# Housekeeping.net
KiCad netlist of a schematic drawn in Altium Designer
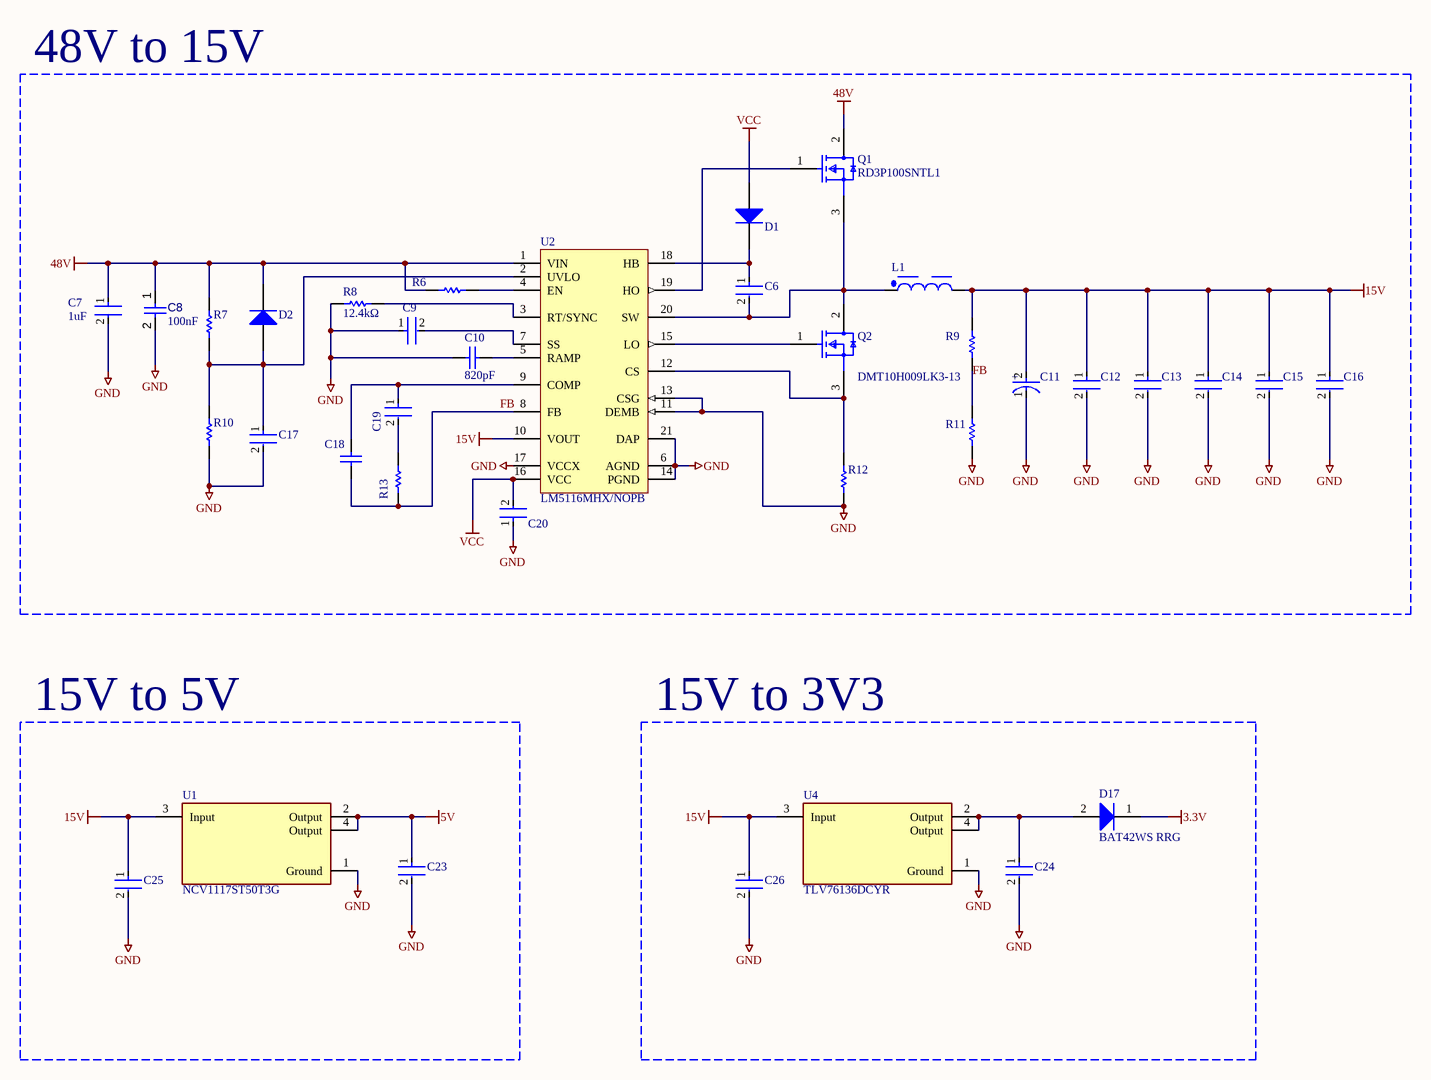
[diagram p0: Housekeeping.SchDoc]

(export (version "E")
  (design (tool "Eeschema 10.0.6"))
  (components
    (comp (ref "C6")
      (value "UMK107AB7105KA-T")
      (footprint "FP-0603-L_1_6_0_15-W_0_8-IPC_C")
      (description "Ceramic Capacitor General Use 1uF ±10% 50V X7R 0603")
      (fields (field (name "TOLERANCE") "10%"))
      (libsource (lib "Altium Content Vault") (part "11868f565c42a9108669ba33697ecf6"))
    )
    (comp (ref "C7")
      (value "C1210C105K1RACTU")
      (footprint "FP-C1210C105K1RACTU-MFG")
      (description "CAP CER 1UF 100V X7R 1210")
      (fields
        (field (name "CAPACITANCE") "1uF")
        (field (name "VOLTAGE") "100V")
        (field (name "TOLERANCE") "10%")
      )
      (libsource (lib "Altium Content Vault") (part "b4654b650e69147ec39a6b967a45e02"))
    )
    (comp (ref "C8")
      (value "100nF")
      (footprint "FP-CL10-IPC_B")
      (fields (field (name "Comment") "CL10B104KC8NNNC"))
      (libsource (lib "CEV Electrical") (part "CAP-NP-2"))
    )
    (comp (ref "C9")
      (value "CL10B104KC8NNNC")
      (footprint "FP-CL10-IPC_A")
      (description "Cap Ceramic 100nF 100V X7R ±10% Pad SMD 0603 +125°C T/R")
      (fields (field (name "TOLERANCE") "10%"))
      (libsource (lib "Altium Content Vault") (part "b4654b650e69147ec39a6b967a45e02"))
    )
    (comp (ref "C10")
      (value "820pF")
      (footprint "0603N821J500CT-Footprint-1")
      (description "0603 Cap Ceramic 820pF 50V C0G 5% - Multilayer Ceramic Capacitors")
      (fields (field (name "TOLERANCE") "5%") (field (name "Comment") "0603N821J500CT"))
      (libsource (lib "CEV Electrical New") (part "0603N821J500CT-Symbol-1"))
    )
    (comp (ref "C11")
      (value "50SVPF10M")
      (footprint "FP-OS-CON-SMT-C6-MFG")
      (description "Conductive Polymer Aluminum Solid Capacitors (OS-CON) 10uF ±20% 50V")
      (fields (field (name "VOLTAGE") "50V") (field (name "TOLERANCE") "20%"))
      (libsource (lib "Altium Content Vault") (part "a00bbbee19879c290e62620ae7e47b1"))
    )
    (comp (ref "C12")
      (value "CL31A106KBHNNNE")
      (footprint "FP-CL31-IPC_C")
      (description "CAP CER 10UF 50V X5R 1206")
      (fields (field (name "TOLERANCE") "10%") (field (name "MANUFACTURER") "Samsung"))
      (libsource (lib "Altium Content Vault") (part "11868f565c42a9108669ba33697ecf6"))
    )
    (comp (ref "C13")
      (value "CL31A106KBHNNNE")
      (footprint "FP-CL31-IPC_C")
      (description "CAP CER 10UF 50V X5R 1206")
      (fields (field (name "TOLERANCE") "10%") (field (name "MANUFACTURER") "Samsung"))
      (libsource (lib "Altium Content Vault") (part "11868f565c42a9108669ba33697ecf6"))
    )
    (comp (ref "C14")
      (value "CL31A106KBHNNNE")
      (footprint "FP-CL31-IPC_C")
      (description "CAP CER 10UF 50V X5R 1206")
      (fields (field (name "TOLERANCE") "10%") (field (name "MANUFACTURER") "Samsung"))
      (libsource (lib "Altium Content Vault") (part "11868f565c42a9108669ba33697ecf6"))
    )
    (comp (ref "C15")
      (value "CL31A106KBHNNNE")
      (footprint "FP-CL31-IPC_C")
      (description "CAP CER 10UF 50V X5R 1206")
      (fields (field (name "TOLERANCE") "10%") (field (name "MANUFACTURER") "Samsung"))
      (libsource (lib "Altium Content Vault") (part "11868f565c42a9108669ba33697ecf6"))
    )
    (comp (ref "C16")
      (value "CL31A106KBHNNNE")
      (footprint "FP-CL31-IPC_C")
      (description "CAP CER 10UF 50V X5R 1206")
      (fields (field (name "TOLERANCE") "10%") (field (name "MANUFACTURER") "Samsung"))
      (libsource (lib "Altium Content Vault") (part "11868f565c42a9108669ba33697ecf6"))
    )
    (comp (ref "C17")
      (value "UMK107AB7105KA-T")
      (footprint "FP-0603-L_1_6_0_15-W_0_8-IPC_C")
      (description "Ceramic Capacitor General Use 1uF ±10% 50V X7R 0603")
      (fields (field (name "TOLERANCE") "10%"))
      (libsource (lib "Altium Content Vault") (part "11868f565c42a9108669ba33697ecf6"))
    )
    (comp (ref "C18")
      (value "CC0603JRNPO9BN101")
      (footprint "CAPC1608X90X40ML10T20")
      (description "Chip Capacitor, 100 pF, +/- 5%, 50 V, -55 to 125 degC, 0603 (1608 Metric), RoHS, Tape and Reel")
      (fields (field (name "TOLERANCE") "5%") (field (name "VOLTAGE") "50V"))
      (libsource (lib "Altium Content Vault") (part "CAP-NP-2"))
    )
    (comp (ref "C19")
      (value "C0603C332J5RACTU")
      (footprint "FP-C0603C-CF-MFG")
      (description "CAP CER 3300PF 50V 5% X7R 0603")
      (fields (field (name "MANUFACTURER") "KEMET") (field (name "TOLERANCE") "0.05"))
      (libsource (lib "Altium Content Vault") (part "b4654b650e69147ec39a6b967a45e02"))
    )
    (comp (ref "C20")
      (value "UMK107AB7105KA-T")
      (footprint "FP-0603-L_1_6_0_15-W_0_8-IPC_C")
      (description "Ceramic Capacitor General Use 1uF ±10% 50V X7R 0603")
      (fields (field (name "TOLERANCE") "10%"))
      (libsource (lib "Altium Content Vault") (part "11868f565c42a9108669ba33697ecf6"))
    )
    (comp (ref "C23")
      (value "CC0603KRX5R6BB106")
      (footprint "FP-CC0603-DC-MFG")
      (description "CAP CER 10UF 10V X5R 0603")
      (fields (field (name "TOLERANCE") "10%"))
      (libsource (lib "Altium Content Vault") (part "b4654b650e69147ec39a6b967a45e02"))
    )
    (comp (ref "C24")
      (value "CC0603KRX5R6BB106")
      (footprint "FP-CC0603-DC-MFG")
      (description "CAP CER 10UF 10V X5R 0603")
      (fields (field (name "TOLERANCE") "10%"))
      (libsource (lib "Altium Content Vault") (part "b4654b650e69147ec39a6b967a45e02"))
    )
    (comp (ref "C25")
      (value "UMK107AB7105KA-T")
      (footprint "FP-0603-L_1_6_0_15-W_0_8-IPC_C")
      (description "Ceramic Capacitor General Use 1uF ±10% 50V X7R 0603")
      (fields (field (name "TOLERANCE") "10%"))
      (libsource (lib "Altium Content Vault") (part "11868f565c42a9108669ba33697ecf6"))
    )
    (comp (ref "C26")
      (value "UMK107AB7105KA-T")
      (footprint "FP-0603-L_1_6_0_15-W_0_8-IPC_C")
      (description "Ceramic Capacitor General Use 1uF ±10% 50V X7R 0603")
      (fields (field (name "TOLERANCE") "10%"))
      (libsource (lib "Altium Content Vault") (part "11868f565c42a9108669ba33697ecf6"))
    )
    (comp (ref "D1")
      (value "LL4148")
      (footprint "FAIR-SOD80-2_V")
      (description "Small Signal Diode, 100 V, 0.2 A, -55 to 175 degC, 2-Pin SOD80, RoHS, Tape and Reel")
      (fields (field (name "MANUFACTURER") "Fairchild"))
      (libsource (lib "Altium Content Vault") (part "D-AK-2"))
    )
    (comp (ref "D2")
      (value "LL4148")
      (footprint "FAIR-SOD80-2_V")
      (description "Small Signal Diode, 100 V, 0.2 A, -55 to 175 degC, 2-Pin SOD80, RoHS, Tape and Reel")
      (fields (field (name "MANUFACTURER") "Fairchild"))
      (libsource (lib "Altium Content Vault") (part "D-AK-2"))
    )
    (comp (ref "D17")
      (value "BAT42WS RRG")
      (footprint "BAT42WS RRG-Footprint-1")
      (description "Schottky Diode, 30V, 0.2A, Sod-323F Rohs Compliant: Yes")
      (libsource (lib "CEV Electrical New") (part "BAT42WS RRG-Symbol-1"))
    )
    (comp (ref "L1")
      (value "7447709390")
      (footprint "WE-PD_1210")
      (description "High Current Inductor, Fixed, 1210, 39 Uh, 4.1 A, .056 Ohm, We-pd Series")
      (fields (field (name "TOLERANCE") "20%"))
      (libsource (lib "Altium Content Vault") (part "Inductor - 2"))
    )
    (comp (ref "Q1")
      (value "RD3P100SNTL1")
      (footprint "DPAK230P990X240-3N")
      (description "Transistor MOSFET N-CH 100V 10A 3-Pin TO-252 Emboss T/R")
      (libsource (lib "CEV Electrical New") (part "RD3P100SNTL1-Symbol-1"))
    )
    (comp (ref "Q2")
      (value "DMT10H009LK3-13")
      (footprint "DPAK229P991X239-3N")
      (description "DMT10H009LK3 series N-Channel Mosfet 100V 90A TO252 (DPAK)")
      (libsource (lib "CEV Electrical New") (part "DMT10H009LK3-13-Symbol-1"))
    )
    (comp (ref "R6")
      (value "RC0603FR-071ML")
      (footprint "RESC1608X55X25LL10T15")
      (description "Chip Resistor, 1 MOhm, +/- 1%, 100 mW, -55 to 155 degC, 0603 (1608 Metric), RoHS, Tape and Reel")
      (fields (field (name "TOLERANCE") "20%"))
      (libsource (lib "") (part "RES-2_1"))
    )
    (comp (ref "R7")
      (value "ERJ-3EKF6192V")
      (footprint "RESC1608X55X30ML15T15")
      (fields (field (name "MANUFACTURER") "Panasonic"))
      (libsource (lib "Altium Content Vault") (part "RES"))
    )
    (comp (ref "R8")
      (value "12.4kΩ")
      (footprint "FP-RC0603-0_55-IPC_C")
      (description "100mW Thick Film Resistors 75V ±100ppm/℃ ±1% 12.4kΩ 0603 Chip Resistor - Surface Mount ROHS")
      (fields (field (name "TOLERANCE") "1%") (field (name "Comment") "RC0603FR-0712K4L"))
      (libsource (lib "CEV Electrical New") (part "1029c3af85768c4190bb7ad29bc67b5"))
    )
    (comp (ref "R9")
      (value "RC0603FR-0716K2L")
      (footprint "RESC1608X55X25NL10T15")
      (fields (field (name "MANUFACTURER") "Yageo"))
      (libsource (lib "Altium Content Vault") (part "RES"))
    )
    (comp (ref "R10")
      (value "ERJ-3EKF3921V")
      (footprint "RESC1608X55X30LL15T15")
      (fields (field (name "MANUFACTURER") "Panasonic"))
      (libsource (lib "Altium Content Vault") (part "RES"))
    )
    (comp (ref "R11")
      (value "ERJ-3EKF1431V")
      (footprint "RESC1608X55X30ML15T15")
      (fields (field (name "MANUFACTURER") "Panasonic"))
      (libsource (lib "Altium Content Vault") (part "RES"))
    )
    (comp (ref "R12")
      (value "ERJ8CWFR024V")
      (footprint "RESC3216X70X50NL05T20")
      (fields (field (name "MANUFACTURER") "Panasonic"))
      (libsource (lib "Altium Content Vault") (part "RES"))
    )
    (comp (ref "R13")
      (value "ERJ3EKF1802V")
      (footprint "RESC1608X55X30LL15T15")
      (fields (field (name "MANUFACTURER") "Panasonic"))
      (libsource (lib "Altium Content Vault") (part "RES-2"))
    )
    (comp (ref "U1")
      (value "NCV1117ST50T3G")
      (footprint "NCV1117ST50T3G-Footprint-1")
      (description "IC REG LDO 5V 1A SOT223 / LDO Regulator Pos 5V 1A Automotive 4-Pin(3+Tab) SOT-223 T/R")
      (libsource (lib "CEV Electrical New") (part "NCV1117ST50T3G-Symbol-1"))
    )
    (comp (ref "U2")
      (value "LM5116MHX/NOPB")
      (footprint "PWP0020A_M")
      (description "Wide Range Synchronous Buck Controller, 20-pin TSSOP-EP, Pb-Free")
      (fields (field (name "MANUFACTURER") "Texas Instruments"))
      (libsource (lib "Altium Content Vault") (part "PM-REG-LM5116MH"))
    )
    (comp (ref "U4")
      (value "TLV76136DCYR")
      (footprint "TLV76136DCYR-Footprint-1")
      (description "1A 16V high-PSRR linear voltage regulator 4-SOT-223 -40 to 125")
      (libsource (lib "CEV Electrical New") (part "TLV76136DCYR-Symbol-1"))
    )
  )
  (nets
    (net (code "1") (name "/FB") (class "Default")
      (node (ref "C18") (pin "1") (pinfunction "1_1") (pintype "passive"))
      (node (ref "R11") (pin "2") (pinfunction "2_2") (pintype "passive"))
      (node (ref "R13") (pin "1") (pinfunction "1_1") (pintype "passive"))
      (node (ref "R9") (pin "1") (pinfunction "1_1") (pintype "passive"))
      (node (ref "U2") (pin "8") (pinfunction "FB_8") (pintype "passive"))
    )
    (net (code "2") (name "3.3V") (class "Default")
      (node (ref "D17") (pin "1") (pinfunction "K_1") (pintype "passive"))
    )
    (net (code "3") (name "5V") (class "Default")
      (node (ref "C23") (pin "1") (pinfunction "1_1") (pintype "passive"))
      (node (ref "U1") (pin "2") (pinfunction "Output_2") (pintype "passive"))
      (node (ref "U1") (pin "4") (pinfunction "Output_4") (pintype "passive"))
    )
    (net (code "4") (name "15V") (class "Default")
      (node (ref "C11") (pin "2") (pinfunction "A_2") (pintype "passive"))
      (node (ref "C12") (pin "1") (pinfunction "1_1") (pintype "passive"))
      (node (ref "C13") (pin "1") (pinfunction "1_1") (pintype "passive"))
      (node (ref "C14") (pin "1") (pinfunction "1_1") (pintype "passive"))
      (node (ref "C15") (pin "1") (pinfunction "1_1") (pintype "passive"))
      (node (ref "C16") (pin "1") (pinfunction "1_1") (pintype "passive"))
      (node (ref "C25") (pin "1") (pinfunction "1_1") (pintype "passive"))
      (node (ref "C26") (pin "1") (pinfunction "1_1") (pintype "passive"))
      (node (ref "L1") (pin "2") (pinfunction "2_2") (pintype "passive"))
      (node (ref "R9") (pin "2") (pinfunction "2_2") (pintype "passive"))
      (node (ref "U1") (pin "3") (pinfunction "Input_3") (pintype "passive"))
      (node (ref "U2") (pin "10") (pinfunction "VOUT_10") (pintype "passive"))
      (node (ref "U4") (pin "3") (pinfunction "Input_3") (pintype "passive"))
    )
    (net (code "5") (name "48V") (class "Default")
      (node (ref "C7") (pin "1") (pinfunction "1_1") (pintype "passive"))
      (node (ref "C8") (pin "1") (pinfunction "1_1") (pintype "passive"))
      (node (ref "D2") (pin "2") (pinfunction "K_2") (pintype "passive"))
      (node (ref "Q1") (pin "2") (pinfunction "2_2") (pintype "passive"))
      (node (ref "R6") (pin "1") (pinfunction "1_1") (pintype "passive"))
      (node (ref "R7") (pin "2") (pinfunction "2_2") (pintype "passive"))
      (node (ref "U2") (pin "1") (pinfunction "VIN_1") (pintype "power_in"))
    )
    (net (code "6") (name "GND") (class "Default")
      (node (ref "C10") (pin "1") (pinfunction "1_1") (pintype "passive"))
      (node (ref "C11") (pin "1") (pinfunction "C_1") (pintype "passive"))
      (node (ref "C12") (pin "2") (pinfunction "2_2") (pintype "passive"))
      (node (ref "C13") (pin "2") (pinfunction "2_2") (pintype "passive"))
      (node (ref "C14") (pin "2") (pinfunction "2_2") (pintype "passive"))
      (node (ref "C15") (pin "2") (pinfunction "2_2") (pintype "passive"))
      (node (ref "C16") (pin "2") (pinfunction "2_2") (pintype "passive"))
      (node (ref "C17") (pin "2") (pinfunction "2_2") (pintype "passive"))
      (node (ref "C20") (pin "1") (pinfunction "1_1") (pintype "passive"))
      (node (ref "C23") (pin "2") (pinfunction "2_2") (pintype "passive"))
      (node (ref "C24") (pin "2") (pinfunction "2_2") (pintype "passive"))
      (node (ref "C25") (pin "2") (pinfunction "2_2") (pintype "passive"))
      (node (ref "C26") (pin "2") (pinfunction "2_2") (pintype "passive"))
      (node (ref "C7") (pin "2") (pinfunction "2_2") (pintype "passive"))
      (node (ref "C8") (pin "2") (pinfunction "2_2") (pintype "passive"))
      (node (ref "C9") (pin "1") (pinfunction "1_1") (pintype "passive"))
      (node (ref "R10") (pin "1") (pinfunction "1_1") (pintype "passive"))
      (node (ref "R11") (pin "1") (pinfunction "1_1") (pintype "passive"))
      (node (ref "R12") (pin "1") (pinfunction "1_1") (pintype "passive"))
      (node (ref "R8") (pin "1") (pinfunction "1_1") (pintype "passive"))
      (node (ref "U1") (pin "1") (pinfunction "Ground_1") (pintype "power_in"))
      (node (ref "U2") (pin "11") (pinfunction "DEMB_11") (pintype "input"))
      (node (ref "U2") (pin "13") (pinfunction "CSG_13") (pintype "input"))
      (node (ref "U2") (pin "14") (pinfunction "PGND_14") (pintype "power_in"))
      (node (ref "U2") (pin "17") (pinfunction "VCCX_17") (pintype "power_in"))
      (node (ref "U2") (pin "21") (pinfunction "DAP_21") (pintype "power_in"))
      (node (ref "U2") (pin "6") (pinfunction "AGND_6") (pintype "power_in"))
      (node (ref "U4") (pin "1") (pinfunction "Ground_1") (pintype "power_in"))
    )
    (net (code "7") (name "Net-(C19-Pad2)") (class "Default")
      (node (ref "C19") (pin "2") (pinfunction "2_2") (pintype "passive"))
      (node (ref "R13") (pin "2") (pinfunction "2_2") (pintype "passive"))
    )
    (net (code "8") (name "Net-(D1-K)") (class "Default")
      (node (ref "C6") (pin "1") (pinfunction "1_1") (pintype "passive"))
      (node (ref "D1") (pin "2") (pinfunction "K_2") (pintype "passive"))
      (node (ref "U2") (pin "18") (pinfunction "HB_18") (pintype "passive"))
    )
    (net (code "9") (name "Net-(D2-A)") (class "Default")
      (node (ref "C17") (pin "1") (pinfunction "1_1") (pintype "passive"))
      (node (ref "D2") (pin "1") (pinfunction "A_1") (pintype "passive"))
      (node (ref "R10") (pin "2") (pinfunction "2_2") (pintype "passive"))
      (node (ref "R7") (pin "1") (pinfunction "1_1") (pintype "passive"))
      (node (ref "U2") (pin "2") (pinfunction "UVLO_2") (pintype "passive"))
    )
    (net (code "10") (name "Net-(D17-A)") (class "Default")
      (node (ref "C24") (pin "1") (pinfunction "1_1") (pintype "passive"))
      (node (ref "D17") (pin "2") (pinfunction "A_2") (pintype "passive"))
      (node (ref "U4") (pin "2") (pinfunction "Output_2") (pintype "passive"))
      (node (ref "U4") (pin "4") (pinfunction "Output_4") (pintype "passive"))
    )
    (net (code "11") (name "Net-(Q1-Gate)") (class "Default")
      (node (ref "Q1") (pin "1") (pinfunction "Gate_1") (pintype "passive"))
      (node (ref "U2") (pin "19") (pinfunction "HO_19") (pintype "output"))
    )
    (net (code "12") (name "Net-(Q2-D)") (class "Default")
      (node (ref "C6") (pin "2") (pinfunction "2_2") (pintype "passive"))
      (node (ref "L1") (pin "1") (pinfunction "1_1") (pintype "passive"))
      (node (ref "Q1") (pin "3") (pinfunction "3_3") (pintype "passive"))
      (node (ref "Q2") (pin "2") (pinfunction "D_2") (pintype "passive"))
      (node (ref "U2") (pin "20") (pinfunction "SW_20") (pintype "power_in"))
    )
    (net (code "13") (name "Net-(Q2-G)") (class "Default")
      (node (ref "Q2") (pin "1") (pinfunction "G_1") (pintype "passive"))
      (node (ref "U2") (pin "15") (pinfunction "LO_15") (pintype "output"))
    )
    (net (code "14") (name "Net-(Q2-S)") (class "Default")
      (node (ref "Q2") (pin "3") (pinfunction "S_3") (pintype "passive"))
      (node (ref "R12") (pin "2") (pinfunction "2_2") (pintype "passive"))
      (node (ref "U2") (pin "12") (pinfunction "CS_12") (pintype "passive"))
    )
    (net (code "15") (name "Net-(U2-COMP)") (class "Default")
      (node (ref "C18") (pin "2") (pinfunction "2_2") (pintype "passive"))
      (node (ref "C19") (pin "1") (pinfunction "1_1") (pintype "passive"))
      (node (ref "U2") (pin "9") (pinfunction "COMP_9") (pintype "passive"))
    )
    (net (code "16") (name "Net-(U2-EN)") (class "Default")
      (node (ref "R6") (pin "2") (pinfunction "2_2") (pintype "passive"))
      (node (ref "U2") (pin "4") (pinfunction "EN_4") (pintype "passive"))
    )
    (net (code "17") (name "Net-(U2-RAMP)") (class "Default")
      (node (ref "C10") (pin "2") (pinfunction "2_2") (pintype "passive"))
      (node (ref "U2") (pin "5") (pinfunction "RAMP_5") (pintype "passive"))
    )
    (net (code "18") (name "Net-(U2-RT{slash}SYNC)") (class "Default")
      (node (ref "R8") (pin "2") (pinfunction "2_2") (pintype "passive"))
      (node (ref "U2") (pin "3") (pinfunction "RT/SYNC_3") (pintype "passive"))
    )
    (net (code "19") (name "Net-(U2-SS)") (class "Default")
      (node (ref "C9") (pin "2") (pinfunction "2_2") (pintype "passive"))
      (node (ref "U2") (pin "7") (pinfunction "SS_7") (pintype "passive"))
    )
    (net (code "20") (name "VCC") (class "Default")
      (node (ref "C20") (pin "2") (pinfunction "2_2") (pintype "passive"))
      (node (ref "D1") (pin "1") (pinfunction "A_1") (pintype "passive"))
      (node (ref "U2") (pin "16") (pinfunction "VCC_16") (pintype "power_in"))
    )
  )
)
